# Breakout_AMT630.net
KiCad netlist of a schematic drawn in EAGLE
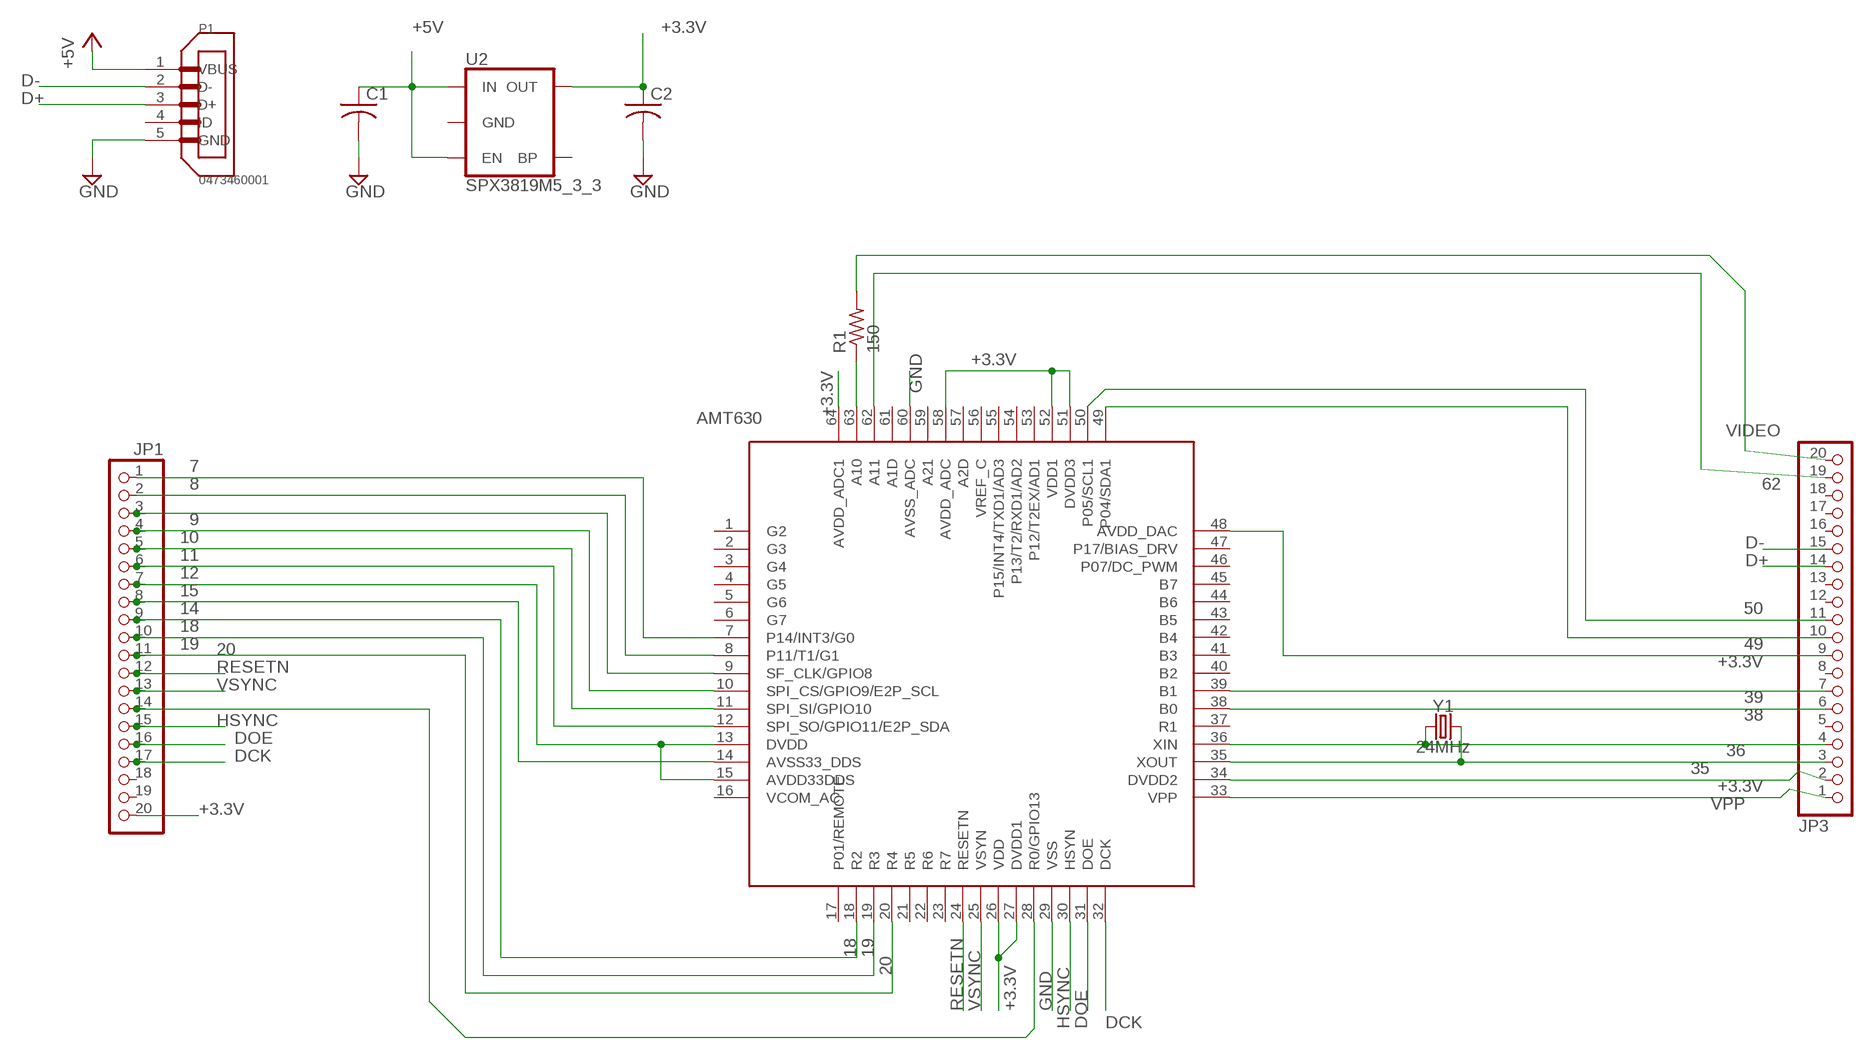
[diagram p0: schematic, sheet 1]

(export (version "E")
  (design (tool "Eeschema 10.0.6"))
  (components
    (comp (ref "C1")
      (value "C-USC0402")
      (footprint "eagle-import:C0402")
      (libsource (lib "eagle-import") (part "C-USC0402"))
    )
    (comp (ref "C2")
      (value "C-USC0402")
      (footprint "eagle-import:C0402")
      (libsource (lib "eagle-import") (part "C-USC0402"))
    )
    (comp (ref "JP1")
      (value "PINHD-1X20-BIG")
      (footprint "eagle-import:1X20-BIG")
      (libsource (lib "eagle-import") (part "PINHD-1X20-BIG"))
    )
    (comp (ref "JP3")
      (value "PINHD-1X20-BIG")
      (footprint "eagle-import:1X20-BIG")
      (libsource (lib "eagle-import") (part "PINHD-1X20-BIG"))
    )
    (comp (ref "P1")
      (value "0473460001")
      (footprint "eagle-import:MOLEX_0473460001")
      (fields (field (name "MF") "Weidmuller"))
      (libsource (lib "eagle-import") (part "0473460001"))
    )
    (comp (ref "R1")
      (value "150")
      (footprint "eagle-import:R0402")
      (libsource (lib "eagle-import") (part "R-US_R0402"))
    )
    (comp (ref "U1")
      (value "AMT630")
      (footprint "eagle-import:QFP50P1200X1200X160-64N")
      (libsource (lib "eagle-import") (part "AMT630"))
    )
    (comp (ref "U2")
      (value "SPX3819M5_3_3")
      (footprint "eagle-import:SOT23-5")
      (libsource (lib "eagle-import") (part "V_REG_SPX3819-SOT23-5"))
    )
    (comp (ref "Y1")
      (value "24MHz")
      (footprint "eagle-import:CRYSTAL-SMD-5X3.2-4PAD")
      (libsource (lib "eagle-import") (part "CRYSTAL-24MHZ{dblquote}"))
    )
  )
  (nets
    (net (code "1") (name "+5V") (class "Default")
      (node (ref "C1") (pin "1") (pinfunction "1_1") (pintype "passive"))
      (node (ref "P1") (pin "1") (pinfunction "VBUS_1") (pintype "power_in"))
      (node (ref "U2") (pin "1") (pinfunction "IN_1") (pintype "input"))
      (node (ref "U2") (pin "3") (pinfunction "EN_3") (pintype "input"))
    )
    (net (code "2") (name "/+3.3V") (class "Default")
      (node (ref "C2") (pin "1") (pinfunction "1_1") (pintype "passive"))
      (node (ref "JP1") (pin "20") (pinfunction "20_20") (pintype "passive"))
      (node (ref "JP3") (pin "2") (pinfunction "2_2") (pintype "passive"))
      (node (ref "JP3") (pin "9") (pinfunction "9_9") (pintype "passive"))
      (node (ref "U1") (pin "26") (pinfunction "VDD_26") (pintype "bidirectional"))
      (node (ref "U1") (pin "27") (pinfunction "DVDD1_27") (pintype "bidirectional"))
      (node (ref "U1") (pin "34") (pinfunction "DVDD2_34") (pintype "bidirectional"))
      (node (ref "U1") (pin "48") (pinfunction "AVDD_DAC_48") (pintype "bidirectional"))
      (node (ref "U1") (pin "51") (pinfunction "DVDD3_51") (pintype "bidirectional"))
      (node (ref "U1") (pin "52") (pinfunction "VDD1_52") (pintype "bidirectional"))
      (node (ref "U1") (pin "58") (pinfunction "AVDD_ADC_58") (pintype "bidirectional"))
      (node (ref "U1") (pin "64") (pinfunction "AVDD_ADC1_64") (pintype "bidirectional"))
      (node (ref "U2") (pin "5") (pinfunction "OUT_5") (pintype "passive"))
    )
    (net (code "3") (name "/7") (class "Default")
      (node (ref "JP1") (pin "1") (pinfunction "1_1") (pintype "passive"))
      (node (ref "U1") (pin "7") (pinfunction "P14/INT3/G0_7") (pintype "bidirectional"))
    )
    (net (code "4") (name "/8") (class "Default")
      (node (ref "JP1") (pin "2") (pinfunction "2_2") (pintype "passive"))
      (node (ref "U1") (pin "8") (pinfunction "P11/T1/G1_8") (pintype "bidirectional"))
    )
    (net (code "5") (name "/9") (class "Default")
      (node (ref "JP1") (pin "3") (pinfunction "3_3") (pintype "passive"))
      (node (ref "U1") (pin "9") (pinfunction "SF_CLK/GPIO8_9") (pintype "bidirectional"))
    )
    (net (code "6") (name "/10") (class "Default")
      (node (ref "JP1") (pin "4") (pinfunction "4_4") (pintype "passive"))
      (node (ref "U1") (pin "10") (pinfunction "SPI_CS/GPIO9/E2P_SCL_10") (pintype "bidirectional"))
    )
    (net (code "7") (name "/11") (class "Default")
      (node (ref "JP1") (pin "5") (pinfunction "5_5") (pintype "passive"))
      (node (ref "U1") (pin "11") (pinfunction "SPI_SI/GPIO10_11") (pintype "bidirectional"))
    )
    (net (code "8") (name "/12") (class "Default")
      (node (ref "JP1") (pin "6") (pinfunction "6_6") (pintype "passive"))
      (node (ref "U1") (pin "12") (pinfunction "SPI_SO/GPIO11/E2P_SDA_12") (pintype "bidirectional"))
    )
    (net (code "9") (name "/14") (class "Default")
      (node (ref "JP1") (pin "8") (pinfunction "8_8") (pintype "passive"))
      (node (ref "U1") (pin "14") (pinfunction "AVSS33_DDS_14") (pintype "bidirectional"))
    )
    (net (code "10") (name "/15") (class "Default")
      (node (ref "JP1") (pin "7") (pinfunction "7_7") (pintype "passive"))
      (node (ref "U1") (pin "13") (pinfunction "DVDD_13") (pintype "bidirectional"))
      (node (ref "U1") (pin "15") (pinfunction "AVDD33DDS_15") (pintype "bidirectional"))
    )
    (net (code "11") (name "/18") (class "Default")
      (node (ref "JP1") (pin "9") (pinfunction "9_9") (pintype "passive"))
      (node (ref "U1") (pin "18") (pinfunction "R2_18") (pintype "bidirectional"))
    )
    (net (code "12") (name "/19") (class "Default")
      (node (ref "JP1") (pin "10") (pinfunction "10_10") (pintype "passive"))
      (node (ref "U1") (pin "19") (pinfunction "R3_19") (pintype "bidirectional"))
    )
    (net (code "13") (name "/20") (class "Default")
      (node (ref "JP1") (pin "11") (pinfunction "11_11") (pintype "passive"))
      (node (ref "U1") (pin "20") (pinfunction "R4_20") (pintype "bidirectional"))
    )
    (net (code "14") (name "/35") (class "Default")
      (node (ref "JP3") (pin "3") (pinfunction "3_3") (pintype "passive"))
      (node (ref "U1") (pin "35") (pinfunction "XOUT_35") (pintype "bidirectional"))
      (node (ref "Y1") (pin "3") (pinfunction "2_3") (pintype "passive"))
    )
    (net (code "15") (name "/36") (class "Default")
      (node (ref "JP3") (pin "4") (pinfunction "4_4") (pintype "passive"))
      (node (ref "U1") (pin "36") (pinfunction "XIN_36") (pintype "bidirectional"))
      (node (ref "Y1") (pin "1") (pinfunction "1_1") (pintype "passive"))
    )
    (net (code "16") (name "/38") (class "Default")
      (node (ref "JP3") (pin "6") (pinfunction "6_6") (pintype "passive"))
      (node (ref "U1") (pin "38") (pinfunction "B0_38") (pintype "bidirectional"))
    )
    (net (code "17") (name "/39") (class "Default")
      (node (ref "JP3") (pin "7") (pinfunction "7_7") (pintype "passive"))
      (node (ref "U1") (pin "39") (pinfunction "B1_39") (pintype "bidirectional"))
    )
    (net (code "18") (name "/49") (class "Default")
      (node (ref "JP3") (pin "10") (pinfunction "10_10") (pintype "passive"))
      (node (ref "U1") (pin "49") (pinfunction "P04/SDA1_49") (pintype "bidirectional"))
    )
    (net (code "19") (name "/50") (class "Default")
      (node (ref "JP3") (pin "11") (pinfunction "11_11") (pintype "passive"))
      (node (ref "U1") (pin "50") (pinfunction "P05/SCL1_50") (pintype "bidirectional"))
    )
    (net (code "20") (name "/62") (class "Default")
      (node (ref "JP3") (pin "19") (pinfunction "19_19") (pintype "passive"))
      (node (ref "U1") (pin "62") (pinfunction "A11_62") (pintype "bidirectional"))
    )
    (net (code "21") (name "/D+") (class "Default")
      (node (ref "JP3") (pin "14") (pinfunction "14_14") (pintype "passive"))
      (node (ref "P1") (pin "3") (pinfunction "D+_3") (pintype "bidirectional"))
    )
    (net (code "22") (name "/D-") (class "Default")
      (node (ref "JP3") (pin "15") (pinfunction "15_15") (pintype "passive"))
      (node (ref "P1") (pin "2") (pinfunction "D-_2") (pintype "bidirectional"))
    )
    (net (code "23") (name "/DCK") (class "Default")
      (node (ref "JP1") (pin "17") (pinfunction "17_17") (pintype "passive"))
      (node (ref "U1") (pin "32") (pinfunction "DCK_32") (pintype "bidirectional"))
    )
    (net (code "24") (name "/DOE") (class "Default")
      (node (ref "JP1") (pin "16") (pinfunction "16_16") (pintype "passive"))
      (node (ref "U1") (pin "31") (pinfunction "DOE_31") (pintype "bidirectional"))
    )
    (net (code "25") (name "/HSYNC") (class "Default")
      (node (ref "JP1") (pin "15") (pinfunction "15_15") (pintype "passive"))
      (node (ref "U1") (pin "30") (pinfunction "HSYN_30") (pintype "bidirectional"))
    )
    (net (code "26") (name "/RESETN") (class "Default")
      (node (ref "JP1") (pin "12") (pinfunction "12_12") (pintype "passive"))
      (node (ref "U1") (pin "24") (pinfunction "RESETN_24") (pintype "bidirectional"))
    )
    (net (code "27") (name "/VIDEO") (class "Default")
      (node (ref "JP3") (pin "20") (pinfunction "20_20") (pintype "passive"))
      (node (ref "R1") (pin "2") (pinfunction "2_2") (pintype "passive"))
    )
    (net (code "28") (name "/VPP") (class "Default")
      (node (ref "JP3") (pin "1") (pinfunction "1_1") (pintype "passive"))
      (node (ref "U1") (pin "33") (pinfunction "VPP_33") (pintype "bidirectional"))
    )
    (net (code "29") (name "/VSYNC") (class "Default")
      (node (ref "JP1") (pin "13") (pinfunction "13_13") (pintype "passive"))
      (node (ref "U1") (pin "25") (pinfunction "VSYN_25") (pintype "bidirectional"))
    )
    (net (code "30") (name "GND") (class "Default")
      (node (ref "C1") (pin "2") (pinfunction "2_2") (pintype "passive"))
      (node (ref "C2") (pin "2") (pinfunction "2_2") (pintype "passive"))
      (node (ref "P1") (pin "5") (pinfunction "GND_5") (pintype "passive"))
      (node (ref "U1") (pin "29") (pinfunction "VSS_29") (pintype "bidirectional"))
      (node (ref "U1") (pin "60") (pinfunction "AVSS_ADC_60") (pintype "bidirectional"))
    )
    (net (code "31") (name "Net-(U1-A10)") (class "Default")
      (node (ref "R1") (pin "1") (pinfunction "1_1") (pintype "passive"))
      (node (ref "U1") (pin "63") (pinfunction "A10_63") (pintype "bidirectional"))
    )
    (net (code "32") (name "Net-(U1-R0{slash}GPIO13)") (class "Default")
      (node (ref "JP1") (pin "14") (pinfunction "14_14") (pintype "passive"))
      (node (ref "U1") (pin "28") (pinfunction "R0/GPIO13_28") (pintype "bidirectional"))
    )
    (net (code "33") (name "unconnected-(JP1-Pad18)") (class "Default")
      (node (ref "JP1") (pin "18") (pinfunction "18_18") (pintype "passive"))
    )
    (net (code "34") (name "unconnected-(JP1-Pad19)") (class "Default")
      (node (ref "JP1") (pin "19") (pinfunction "19_19") (pintype "passive"))
    )
    (net (code "35") (name "unconnected-(JP3-Pad5)") (class "Default")
      (node (ref "JP3") (pin "5") (pinfunction "5_5") (pintype "passive"))
    )
    (net (code "36") (name "unconnected-(JP3-Pad8)") (class "Default")
      (node (ref "JP3") (pin "8") (pinfunction "8_8") (pintype "passive"))
    )
    (net (code "37") (name "unconnected-(JP3-Pad12)") (class "Default")
      (node (ref "JP3") (pin "12") (pinfunction "12_12") (pintype "passive"))
    )
    (net (code "38") (name "unconnected-(JP3-Pad13)") (class "Default")
      (node (ref "JP3") (pin "13") (pinfunction "13_13") (pintype "passive"))
    )
    (net (code "39") (name "unconnected-(JP3-Pad16)") (class "Default")
      (node (ref "JP3") (pin "16") (pinfunction "16_16") (pintype "passive"))
    )
    (net (code "40") (name "unconnected-(JP3-Pad17)") (class "Default")
      (node (ref "JP3") (pin "17") (pinfunction "17_17") (pintype "passive"))
    )
    (net (code "41") (name "unconnected-(JP3-Pad18)") (class "Default")
      (node (ref "JP3") (pin "18") (pinfunction "18_18") (pintype "passive"))
    )
    (net (code "42") (name "unconnected-(P1-ID-Pad4)") (class "Default")
      (node (ref "P1") (pin "4") (pinfunction "ID_4") (pintype "bidirectional"))
    )
    (net (code "43") (name "unconnected-(U1-A1D-Pad61)") (class "Default")
      (node (ref "U1") (pin "61") (pinfunction "A1D_61") (pintype "bidirectional"))
    )
    (net (code "44") (name "unconnected-(U1-A2D-Pad57)") (class "Default")
      (node (ref "U1") (pin "57") (pinfunction "A2D_57") (pintype "bidirectional"))
    )
    (net (code "45") (name "unconnected-(U1-A21-Pad59)") (class "Default")
      (node (ref "U1") (pin "59") (pinfunction "A21_59") (pintype "bidirectional"))
    )
    (net (code "46") (name "unconnected-(U1-B2-Pad40)") (class "Default")
      (node (ref "U1") (pin "40") (pinfunction "B2_40") (pintype "bidirectional"))
    )
    (net (code "47") (name "unconnected-(U1-B3-Pad41)") (class "Default")
      (node (ref "U1") (pin "41") (pinfunction "B3_41") (pintype "bidirectional"))
    )
    (net (code "48") (name "unconnected-(U1-B4-Pad42)") (class "Default")
      (node (ref "U1") (pin "42") (pinfunction "B4_42") (pintype "bidirectional"))
    )
    (net (code "49") (name "unconnected-(U1-B5-Pad43)") (class "Default")
      (node (ref "U1") (pin "43") (pinfunction "B5_43") (pintype "bidirectional"))
    )
    (net (code "50") (name "unconnected-(U1-B6-Pad44)") (class "Default")
      (node (ref "U1") (pin "44") (pinfunction "B6_44") (pintype "bidirectional"))
    )
    (net (code "51") (name "unconnected-(U1-B7-Pad45)") (class "Default")
      (node (ref "U1") (pin "45") (pinfunction "B7_45") (pintype "bidirectional"))
    )
    (net (code "52") (name "unconnected-(U1-G2-Pad1)") (class "Default")
      (node (ref "U1") (pin "1") (pinfunction "G2_1") (pintype "bidirectional"))
    )
    (net (code "53") (name "unconnected-(U1-G3-Pad2)") (class "Default")
      (node (ref "U1") (pin "2") (pinfunction "G3_2") (pintype "bidirectional"))
    )
    (net (code "54") (name "unconnected-(U1-G4-Pad3)") (class "Default")
      (node (ref "U1") (pin "3") (pinfunction "G4_3") (pintype "bidirectional"))
    )
    (net (code "55") (name "unconnected-(U1-G5-Pad4)") (class "Default")
      (node (ref "U1") (pin "4") (pinfunction "G5_4") (pintype "bidirectional"))
    )
    (net (code "56") (name "unconnected-(U1-G6-Pad5)") (class "Default")
      (node (ref "U1") (pin "5") (pinfunction "G6_5") (pintype "bidirectional"))
    )
    (net (code "57") (name "unconnected-(U1-G7-Pad6)") (class "Default")
      (node (ref "U1") (pin "6") (pinfunction "G7_6") (pintype "bidirectional"))
    )
    (net (code "58") (name "unconnected-(U1-P01{slash}REMOTE-Pad17)") (class "Default")
      (node (ref "U1") (pin "17") (pinfunction "P01/REMOTE_17") (pintype "bidirectional"))
    )
    (net (code "59") (name "unconnected-(U1-P07{slash}DC_PWM-Pad46)") (class "Default")
      (node (ref "U1") (pin "46") (pinfunction "P07/DC_PWM_46") (pintype "bidirectional"))
    )
    (net (code "60") (name "unconnected-(U1-P12{slash}T2EX{slash}AD1-Pad53)") (class "Default")
      (node (ref "U1") (pin "53") (pinfunction "P12/T2EX/AD1_53") (pintype "bidirectional"))
    )
    (net (code "61") (name "unconnected-(U1-P13{slash}T2{slash}RXD1{slash}AD2-Pad54)") (class "Default")
      (node (ref "U1") (pin "54") (pinfunction "P13/T2/RXD1/AD2_54") (pintype "bidirectional"))
    )
    (net (code "62") (name "unconnected-(U1-P15{slash}INT4{slash}TXD1{slash}AD3-Pad55)") (class "Default")
      (node (ref "U1") (pin "55") (pinfunction "P15/INT4/TXD1/AD3_55") (pintype "bidirectional"))
    )
    (net (code "63") (name "unconnected-(U1-P17{slash}BIAS_DRV-Pad47)") (class "Default")
      (node (ref "U1") (pin "47") (pinfunction "P17/BIAS_DRV_47") (pintype "bidirectional"))
    )
    (net (code "64") (name "unconnected-(U1-R1-Pad37)") (class "Default")
      (node (ref "U1") (pin "37") (pinfunction "R1_37") (pintype "bidirectional"))
    )
    (net (code "65") (name "unconnected-(U1-R5-Pad21)") (class "Default")
      (node (ref "U1") (pin "21") (pinfunction "R5_21") (pintype "bidirectional"))
    )
    (net (code "66") (name "unconnected-(U1-R6-Pad22)") (class "Default")
      (node (ref "U1") (pin "22") (pinfunction "R6_22") (pintype "bidirectional"))
    )
    (net (code "67") (name "unconnected-(U1-R7-Pad23)") (class "Default")
      (node (ref "U1") (pin "23") (pinfunction "R7_23") (pintype "bidirectional"))
    )
    (net (code "68") (name "unconnected-(U1-VCOM_AC-Pad16)") (class "Default")
      (node (ref "U1") (pin "16") (pinfunction "VCOM_AC_16") (pintype "bidirectional"))
    )
    (net (code "69") (name "unconnected-(U1-VREF_C-Pad56)") (class "Default")
      (node (ref "U1") (pin "56") (pinfunction "VREF_C_56") (pintype "bidirectional"))
    )
    (net (code "70") (name "unconnected-(U2-BP-Pad4)") (class "Default")
      (node (ref "U2") (pin "4") (pinfunction "BP_4") (pintype "input"))
    )
    (net (code "71") (name "unconnected-(U2-GND-Pad2)") (class "Default")
      (node (ref "U2") (pin "2") (pinfunction "GND_2") (pintype "input"))
    )
  )
)
